# USB_Switcher_v0_0.net
KiCad netlist of a schematic drawn in Altium Designer
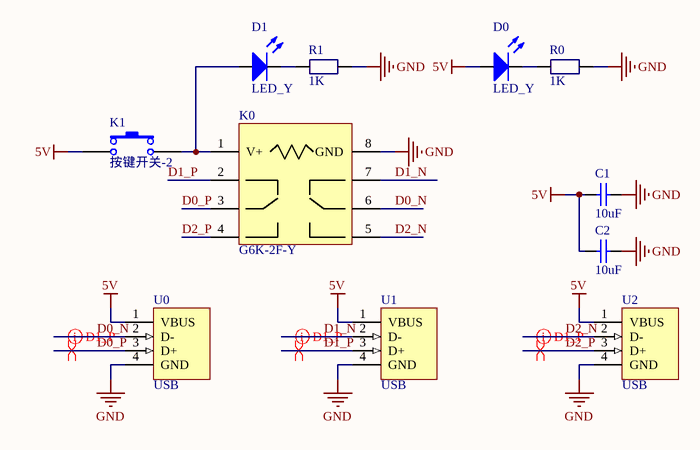
[diagram p0: USB_Switcher_v0.0.SchDoc]

(export (version "E")
  (design (tool "Eeschema 10.0.6"))
  (components
    (comp (ref "C1")
      (value "10uF")
      (footprint "1206-C")
      (description "电容类")
      (libsource (lib "海鲜的元件库（总成）") (part "CAP-无极性"))
    )
    (comp (ref "C2")
      (value "10uF")
      (footprint "1206-C")
      (description "电容类")
      (libsource (lib "海鲜的元件库（总成）") (part "CAP-无极性"))
    )
    (comp (ref "D0")
      (value "LED_Y")
      (footprint "LED-0805-YEL")
      (description "LED")
      (libsource (lib "海鲜的元件库（总成）") (part "LED"))
    )
    (comp (ref "D1")
      (value "LED_Y")
      (footprint "LED-0805-YEL")
      (description "LED")
      (libsource (lib "海鲜的元件库（总成）") (part "LED"))
    )
    (comp (ref "K0")
      (value "G6K-2F-Y")
      (footprint "G6K-2F-Y")
      (description "双刀信号继电器")
      (libsource (lib "海鲜的元件库（总成）") (part "G6K"))
    )
    (comp (ref "K1")
      (value "按键开关-2")
      (footprint "KAN9A_2P_ON-OFF")
      (libsource (lib "海鲜的元件库（总成）") (part "按键开关-2"))
    )
    (comp (ref "R0")
      (value "1K")
      (footprint "0402-R")
      (description "电阻类")
      (libsource (lib "海鲜的元件库（总成）") (part "RES"))
    )
    (comp (ref "R1")
      (value "1K")
      (footprint "0402-R")
      (description "电阻类")
      (libsource (lib "海鲜的元件库（总成）") (part "RES"))
    )
    (comp (ref "U0")
      (value "USB")
      (footprint "USB-A")
      (description "USB-2.0")
      (libsource (lib "海鲜的元件库（总成）") (part "USB-2.0"))
    )
    (comp (ref "U1")
      (value "USB")
      (footprint "USB-A")
      (description "USB-2.0")
      (libsource (lib "海鲜的元件库（总成）") (part "USB-2.0"))
    )
    (comp (ref "U2")
      (value "USB")
      (footprint "USB-A")
      (description "USB-2.0")
      (libsource (lib "海鲜的元件库（总成）") (part "USB-2.0"))
    )
  )
  (nets
    (net (code "1") (name "/D0_N") (class "Default")
      (node (ref "K0") (pin "6") (pinfunction "6_6") (pintype "passive"))
      (node (ref "U0") (pin "2") (pinfunction "D-_2") (pintype "input"))
    )
    (net (code "2") (name "/D0_P") (class "Default")
      (node (ref "K0") (pin "3") (pinfunction "3_3") (pintype "passive"))
      (node (ref "U0") (pin "3") (pinfunction "D+_3") (pintype "input"))
    )
    (net (code "3") (name "/D1_N") (class "Default")
      (node (ref "K0") (pin "7") (pinfunction "7_7") (pintype "passive"))
      (node (ref "U1") (pin "2") (pinfunction "D-_2") (pintype "input"))
    )
    (net (code "4") (name "/D1_P") (class "Default")
      (node (ref "K0") (pin "2") (pinfunction "2_2") (pintype "passive"))
      (node (ref "U1") (pin "3") (pinfunction "D+_3") (pintype "input"))
    )
    (net (code "5") (name "/D2_N") (class "Default")
      (node (ref "K0") (pin "5") (pinfunction "5_5") (pintype "passive"))
      (node (ref "U2") (pin "2") (pinfunction "D-_2") (pintype "input"))
    )
    (net (code "6") (name "/D2_P") (class "Default")
      (node (ref "K0") (pin "4") (pinfunction "4_4") (pintype "passive"))
      (node (ref "U2") (pin "3") (pinfunction "D+_3") (pintype "input"))
    )
    (net (code "7") (name "5V") (class "Default")
      (node (ref "C1") (pin "2") (pinfunction "2_2") (pintype "passive"))
      (node (ref "C2") (pin "2") (pinfunction "2_2") (pintype "passive"))
      (node (ref "D0") (pin "1") (pinfunction "1_1") (pintype "passive"))
      (node (ref "K1") (pin "1") (pinfunction "1_1") (pintype "passive"))
      (node (ref "U0") (pin "1") (pinfunction "VBUS_1") (pintype "power_in"))
      (node (ref "U1") (pin "1") (pinfunction "VBUS_1") (pintype "power_in"))
      (node (ref "U2") (pin "1") (pinfunction "VBUS_1") (pintype "power_in"))
    )
    (net (code "8") (name "GND") (class "Default")
      (node (ref "C1") (pin "1") (pinfunction "1_1") (pintype "passive"))
      (node (ref "C2") (pin "1") (pinfunction "1_1") (pintype "passive"))
      (node (ref "K0") (pin "8") (pinfunction "GND_8") (pintype "passive"))
      (node (ref "R0") (pin "2") (pintype "passive"))
      (node (ref "R1") (pin "2") (pintype "passive"))
      (node (ref "U0") (pin "4") (pinfunction "GND_4") (pintype "power_in"))
      (node (ref "U1") (pin "4") (pinfunction "GND_4") (pintype "power_in"))
      (node (ref "U2") (pin "4") (pinfunction "GND_4") (pintype "power_in"))
    )
    (net (code "9") (name "Net-(D0-Pad2)") (class "Default")
      (node (ref "D0") (pin "2") (pinfunction "2_2") (pintype "passive"))
      (node (ref "R0") (pin "1") (pintype "passive"))
    )
    (net (code "10") (name "Net-(D1-Pad2)") (class "Default")
      (node (ref "D1") (pin "2") (pinfunction "2_2") (pintype "passive"))
      (node (ref "R1") (pin "1") (pintype "passive"))
    )
    (net (code "11") (name "Net-(K0-V+)") (class "Default")
      (node (ref "D1") (pin "1") (pinfunction "1_1") (pintype "passive"))
      (node (ref "K0") (pin "1") (pinfunction "V+_1") (pintype "passive"))
      (node (ref "K1") (pin "2") (pinfunction "2_2") (pintype "passive"))
    )
  )
)
